# pcb_3.net
KiCad netlist of a schematic drawn in EAGLE
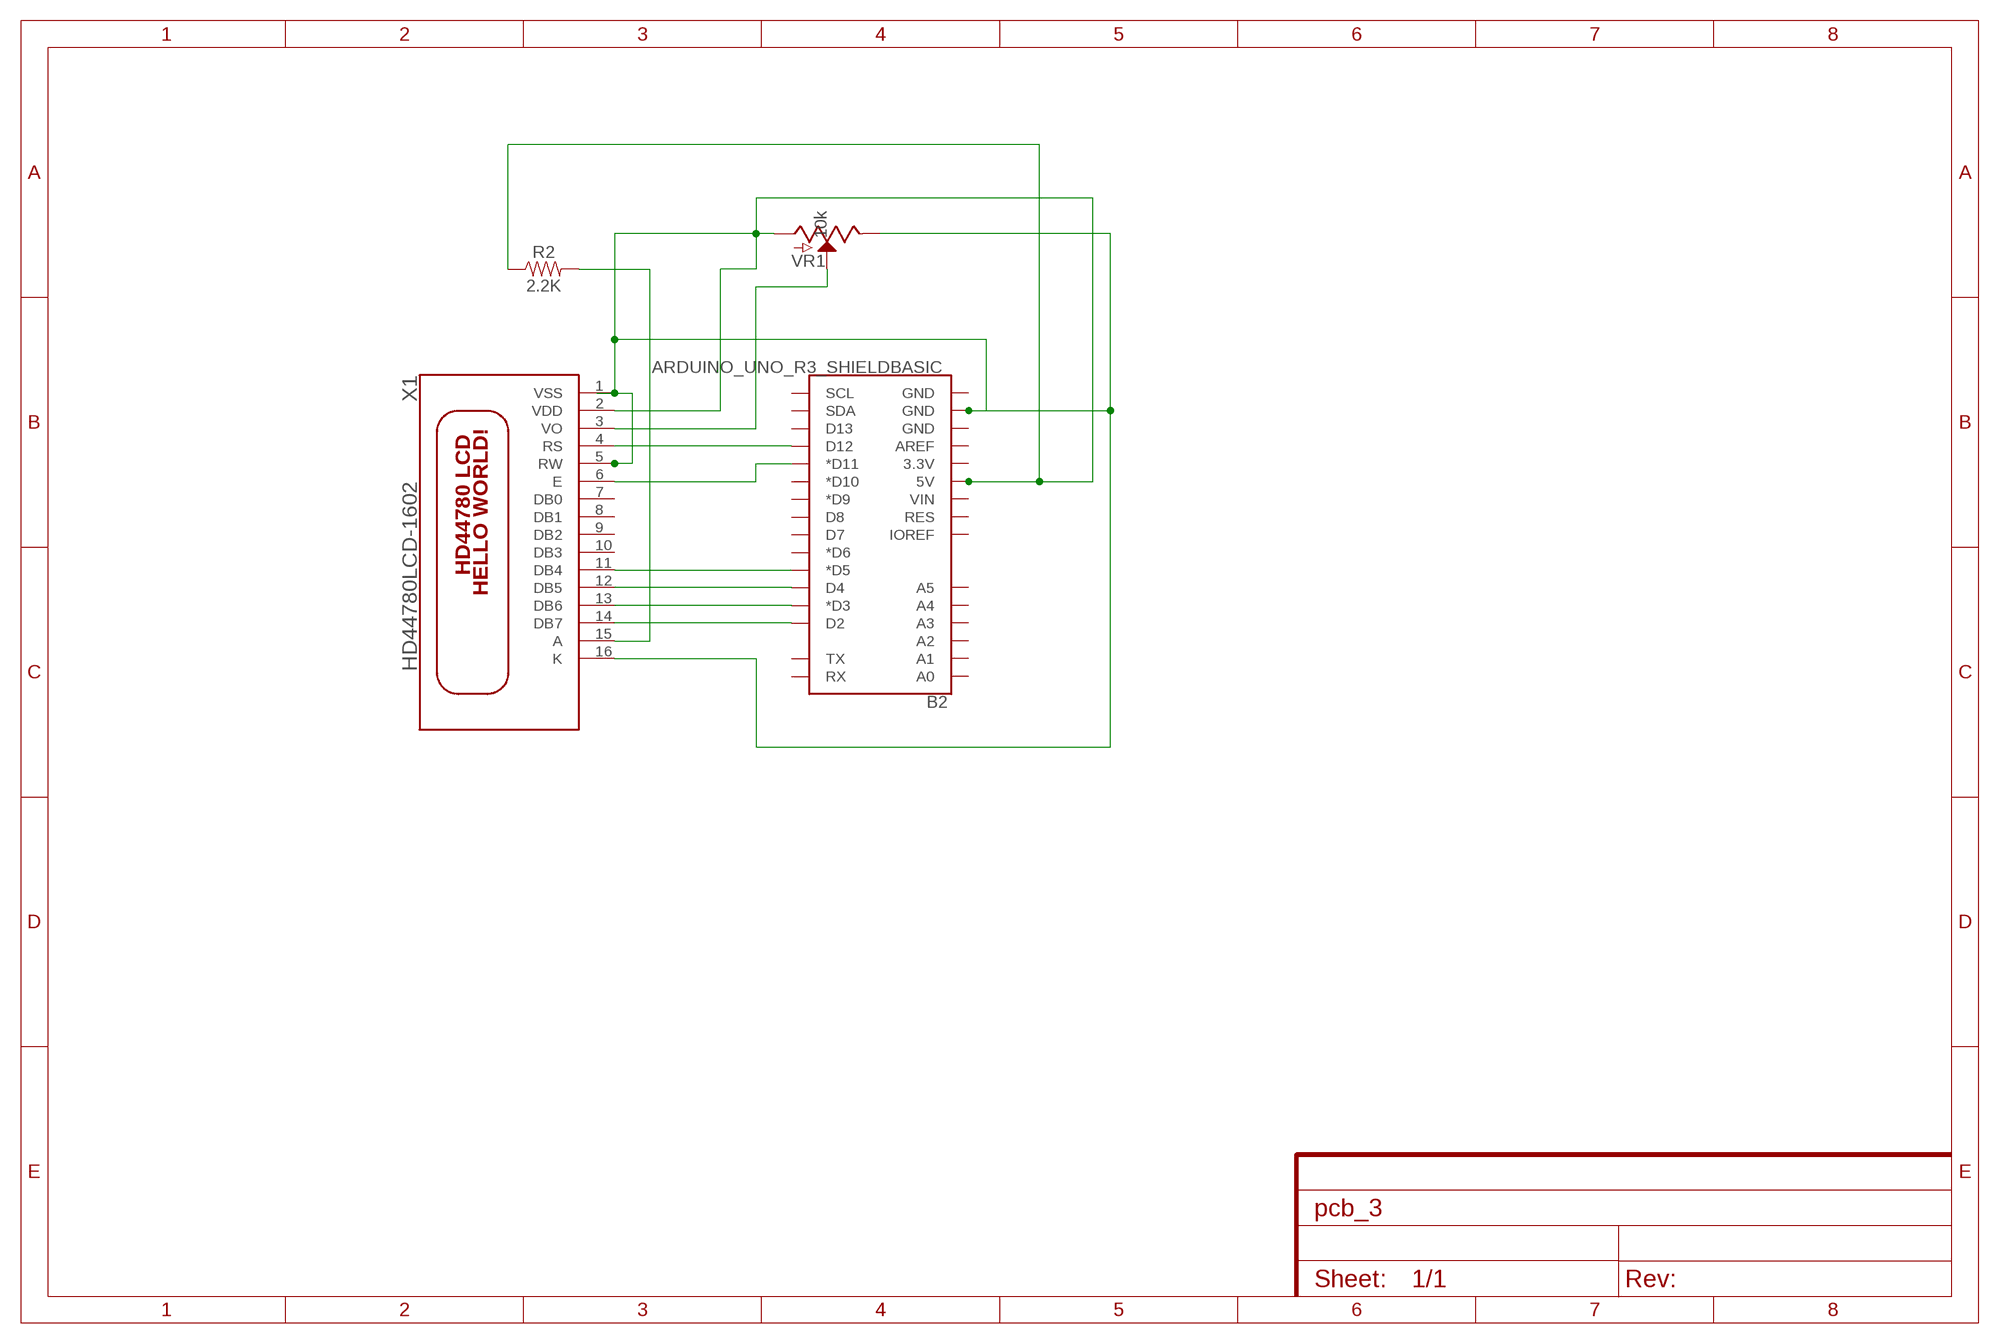
[diagram p0: schematic, sheet 1]

(export (version "E")
  (design (tool "Eeschema 10.0.6"))
  (components
    (comp (ref "B2")
      (value "ARDUINO_UNO_R3_SHIELDBASIC")
      (footprint "eagle-import:UNO_R3_SHIELD")
      (libsource (lib "eagle-import") (part "ARDUINO_UNO_R3_SHIELDBASIC"))
    )
    (comp (ref "R2")
      (value "2.2K")
      (footprint "eagle-import:0402")
      (libsource (lib "eagle-import") (part "2.2KOHM-0402-1/16W-1%"))
    )
    (comp (ref "VR1")
      (value "10k")
      (footprint "eagle-import:POT-PTH-ALPS-KIT")
      (libsource (lib "eagle-import") (part "POTENTIOMETER-PTH-9MM-1/20W-20%-KIT"))
    )
    (comp (ref "X1")
      (value "HD44780LCD-1602")
      (footprint "eagle-import:LCD1602")
      (libsource (lib "eagle-import") (part "HD44780LCD-1602"))
    )
  )
  (nets
    (net (code "1") (name "Net-(B2-*D3)") (class "Default")
      (node (ref "B2") (pin "D3") (pinfunction "*D3_D3") (pintype "bidirectional"))
      (node (ref "X1") (pin "13") (pinfunction "DB6_13") (pintype "bidirectional"))
    )
    (net (code "2") (name "Net-(B2-*D5)") (class "Default")
      (node (ref "B2") (pin "D5") (pinfunction "*D5_D5") (pintype "bidirectional"))
      (node (ref "X1") (pin "11") (pinfunction "DB4_11") (pintype "bidirectional"))
    )
    (net (code "3") (name "Net-(B2-*D11)") (class "Default")
      (node (ref "B2") (pin "D11") (pinfunction "*D11_D11") (pintype "bidirectional"))
      (node (ref "X1") (pin "6") (pinfunction "E_6") (pintype "input"))
    )
    (net (code "4") (name "Net-(VR1-A)") (class "Default")
      (node (ref "B2") (pin "5V") (pinfunction "5V_5V") (pintype "bidirectional"))
      (node (ref "B2") (pin "GND@1") (pinfunction "GND_GND@1") (pintype "bidirectional"))
      (node (ref "R2") (pin "1") (pinfunction "1_1") (pintype "passive"))
      (node (ref "VR1") (pin "P$1") (pinfunction "E_P$1") (pintype "passive"))
      (node (ref "VR1") (pin "P$3") (pinfunction "A_P$3") (pintype "passive"))
      (node (ref "X1") (pin "1") (pinfunction "VSS_1") (pintype "power_in"))
      (node (ref "X1") (pin "16") (pinfunction "K_16") (pintype "input"))
      (node (ref "X1") (pin "2") (pinfunction "VDD_2") (pintype "power_in"))
      (node (ref "X1") (pin "5") (pinfunction "RW_5") (pintype "input"))
    )
    (net (code "5") (name "Net-(VR1-S)") (class "Default")
      (node (ref "VR1") (pin "P$2") (pinfunction "S_P$2") (pintype "passive"))
      (node (ref "X1") (pin "3") (pinfunction "VO_3") (pintype "input"))
    )
    (net (code "6") (name "Net-(X1-A)") (class "Default")
      (node (ref "R2") (pin "2") (pinfunction "2_2") (pintype "passive"))
      (node (ref "X1") (pin "15") (pinfunction "A_15") (pintype "input"))
    )
    (net (code "7") (name "Net-(X1-DB5)") (class "Default")
      (node (ref "B2") (pin "D4") (pinfunction "D4_D4") (pintype "bidirectional"))
      (node (ref "X1") (pin "12") (pinfunction "DB5_12") (pintype "bidirectional"))
    )
    (net (code "8") (name "Net-(X1-DB7)") (class "Default")
      (node (ref "B2") (pin "D2") (pinfunction "D2_D2") (pintype "bidirectional"))
      (node (ref "X1") (pin "14") (pinfunction "DB7_14") (pintype "bidirectional"))
    )
    (net (code "9") (name "Net-(X1-RS)") (class "Default")
      (node (ref "B2") (pin "D12") (pinfunction "D12_D12") (pintype "bidirectional"))
      (node (ref "X1") (pin "4") (pinfunction "RS_4") (pintype "input"))
    )
    (net (code "10") (name "unconnected-(B2-*D6-PadD6)") (class "Default")
      (node (ref "B2") (pin "D6") (pinfunction "*D6_D6") (pintype "bidirectional"))
    )
    (net (code "11") (name "unconnected-(B2-*D9-PadD9)") (class "Default")
      (node (ref "B2") (pin "D9") (pinfunction "*D9_D9") (pintype "bidirectional"))
    )
    (net (code "12") (name "unconnected-(B2-*D10-PadD10)") (class "Default")
      (node (ref "B2") (pin "D10") (pinfunction "*D10_D10") (pintype "bidirectional"))
    )
    (net (code "13") (name "unconnected-(B2-GND-PadGND@0)") (class "Default")
      (node (ref "B2") (pin "GND@0") (pinfunction "GND_GND@0") (pintype "bidirectional"))
    )
    (net (code "14") (name "unconnected-(B2-GND-PadGND@2)") (class "Default")
      (node (ref "B2") (pin "GND@2") (pinfunction "GND_GND@2") (pintype "bidirectional"))
    )
    (net (code "15") (name "unconnected-(B2-Pad3.3V)") (class "Default")
      (node (ref "B2") (pin "3.3V") (pinfunction "3.3V_3.3V") (pintype "bidirectional"))
    )
    (net (code "16") (name "unconnected-(B2-PadA0)") (class "Default")
      (node (ref "B2") (pin "A0") (pinfunction "A0_A0") (pintype "bidirectional"))
    )
    (net (code "17") (name "unconnected-(B2-PadA1)") (class "Default")
      (node (ref "B2") (pin "A1") (pinfunction "A1_A1") (pintype "bidirectional"))
    )
    (net (code "18") (name "unconnected-(B2-PadA2)") (class "Default")
      (node (ref "B2") (pin "A2") (pinfunction "A2_A2") (pintype "bidirectional"))
    )
    (net (code "19") (name "unconnected-(B2-PadA3)") (class "Default")
      (node (ref "B2") (pin "A3") (pinfunction "A3_A3") (pintype "bidirectional"))
    )
    (net (code "20") (name "unconnected-(B2-PadA4)") (class "Default")
      (node (ref "B2") (pin "A4") (pinfunction "A4_A4") (pintype "bidirectional"))
    )
    (net (code "21") (name "unconnected-(B2-PadA5)") (class "Default")
      (node (ref "B2") (pin "A5") (pinfunction "A5_A5") (pintype "bidirectional"))
    )
    (net (code "22") (name "unconnected-(B2-PadAREF)") (class "Default")
      (node (ref "B2") (pin "AREF") (pinfunction "AREF_AREF") (pintype "bidirectional"))
    )
    (net (code "23") (name "unconnected-(B2-PadD7)") (class "Default")
      (node (ref "B2") (pin "D7") (pinfunction "D7_D7") (pintype "bidirectional"))
    )
    (net (code "24") (name "unconnected-(B2-PadD8)") (class "Default")
      (node (ref "B2") (pin "D8") (pinfunction "D8_D8") (pintype "bidirectional"))
    )
    (net (code "25") (name "unconnected-(B2-PadD13)") (class "Default")
      (node (ref "B2") (pin "D13") (pinfunction "D13_D13") (pintype "bidirectional"))
    )
    (net (code "26") (name "unconnected-(B2-PadIOREF)") (class "Default")
      (node (ref "B2") (pin "IOREF") (pinfunction "IOREF_IOREF") (pintype "bidirectional"))
    )
    (net (code "27") (name "unconnected-(B2-PadRES)") (class "Default")
      (node (ref "B2") (pin "RES") (pinfunction "RES_RES") (pintype "bidirectional"))
    )
    (net (code "28") (name "unconnected-(B2-PadRX)") (class "Default")
      (node (ref "B2") (pin "RX") (pinfunction "RX_RX") (pintype "bidirectional"))
    )
    (net (code "29") (name "unconnected-(B2-PadSCL)") (class "Default")
      (node (ref "B2") (pin "SCL") (pinfunction "SCL_SCL") (pintype "bidirectional"))
    )
    (net (code "30") (name "unconnected-(B2-PadSDA)") (class "Default")
      (node (ref "B2") (pin "SDA") (pinfunction "SDA_SDA") (pintype "bidirectional"))
    )
    (net (code "31") (name "unconnected-(B2-PadTX)") (class "Default")
      (node (ref "B2") (pin "TX") (pinfunction "TX_TX") (pintype "bidirectional"))
    )
    (net (code "32") (name "unconnected-(B2-PadVIN)") (class "Default")
      (node (ref "B2") (pin "VIN") (pinfunction "VIN_VIN") (pintype "bidirectional"))
    )
    (net (code "33") (name "unconnected-(X1-DB0-Pad7)") (class "Default")
      (node (ref "X1") (pin "7") (pinfunction "DB0_7") (pintype "bidirectional"))
    )
    (net (code "34") (name "unconnected-(X1-DB1-Pad8)") (class "Default")
      (node (ref "X1") (pin "8") (pinfunction "DB1_8") (pintype "bidirectional"))
    )
    (net (code "35") (name "unconnected-(X1-DB2-Pad9)") (class "Default")
      (node (ref "X1") (pin "9") (pinfunction "DB2_9") (pintype "bidirectional"))
    )
    (net (code "36") (name "unconnected-(X1-DB3-Pad10)") (class "Default")
      (node (ref "X1") (pin "10") (pinfunction "DB3_10") (pintype "bidirectional"))
    )
  )
)
